# keyboard.net
KiCad netlist of a schematic drawn in Altium Designer
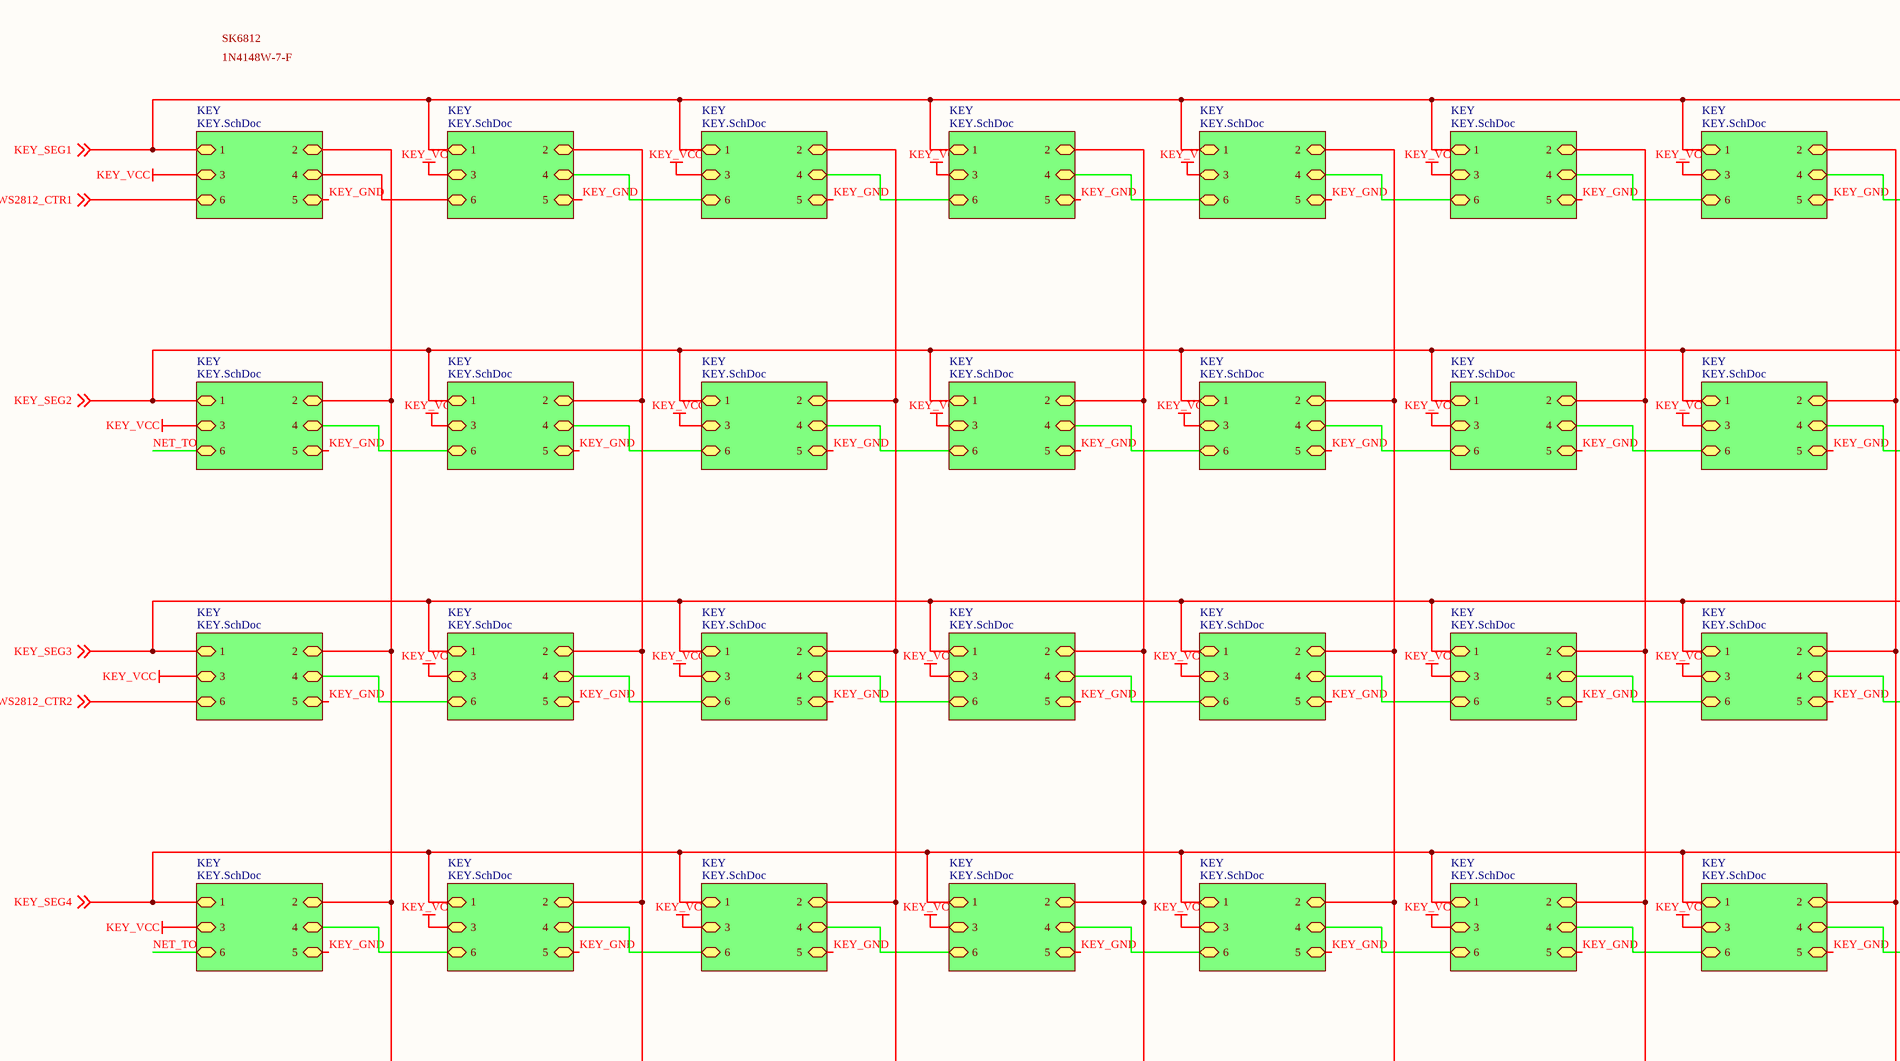
[diagram p0: keyboard.SchDoc, top left]
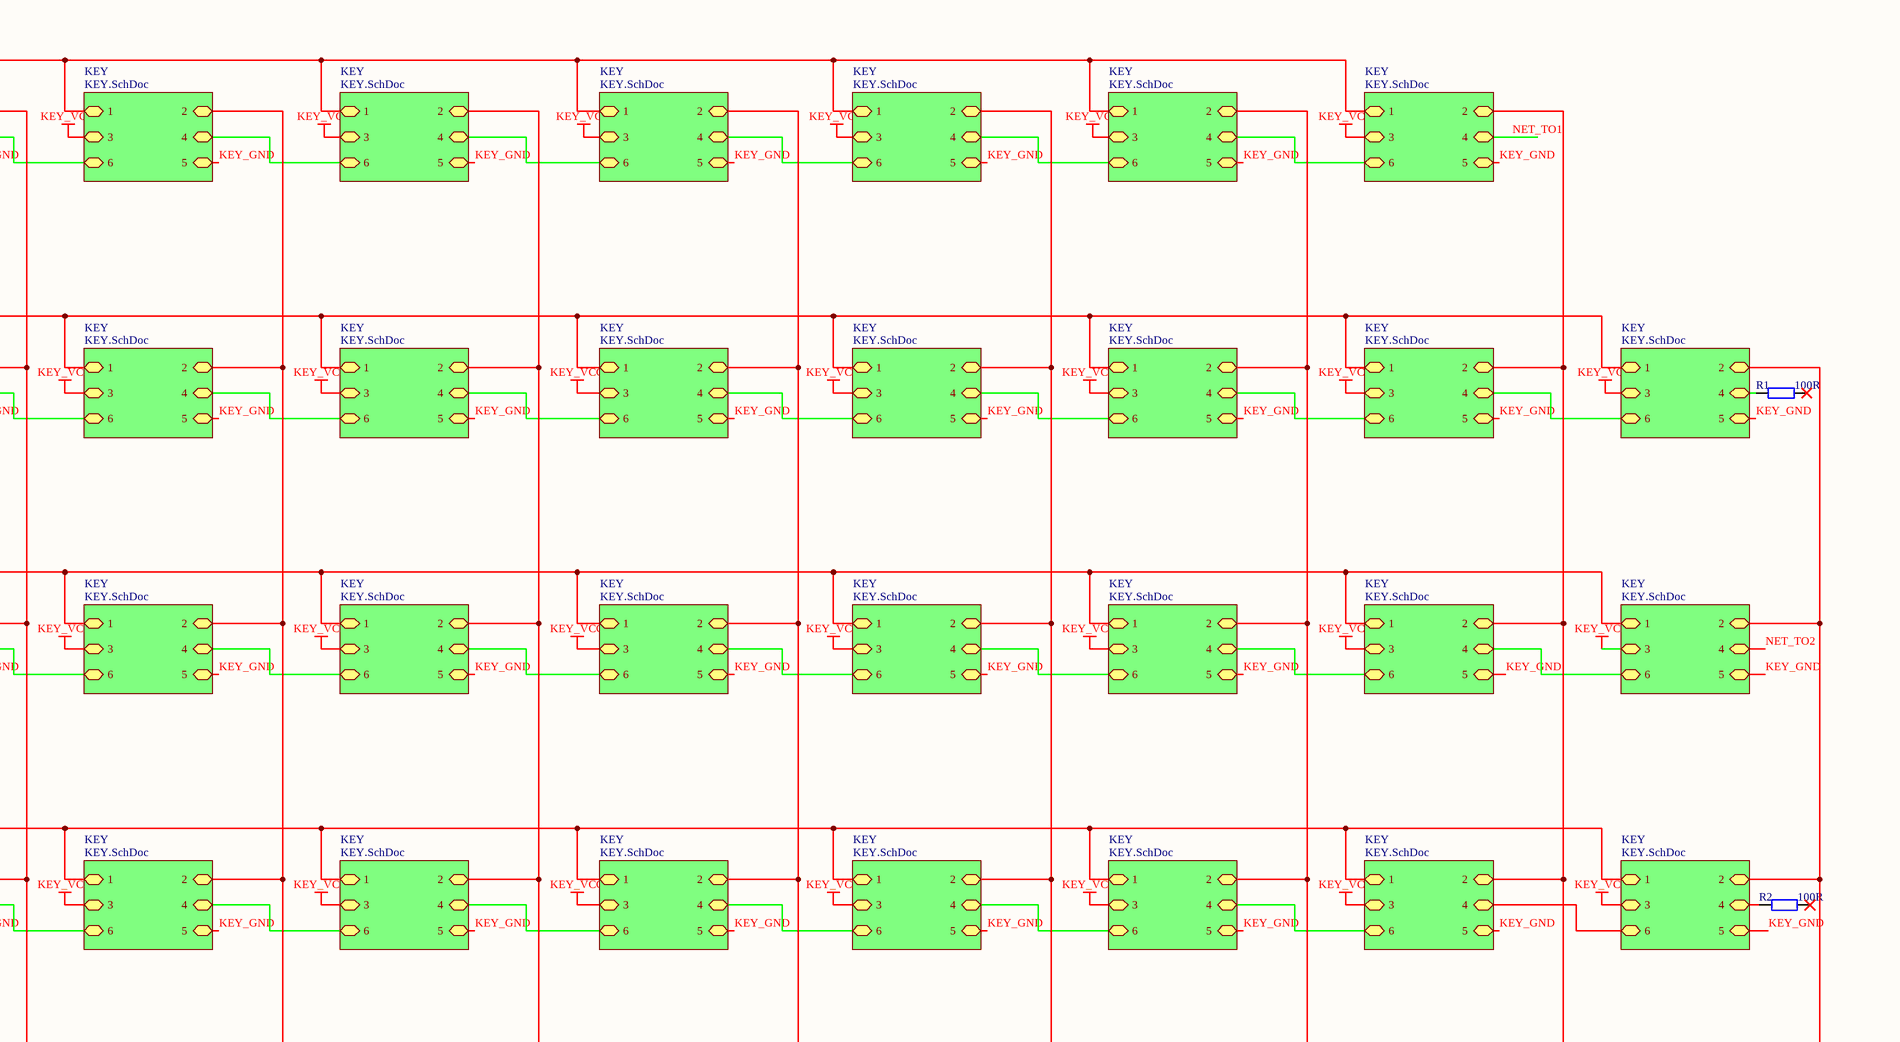
[diagram p1: keyboard.SchDoc, top right]
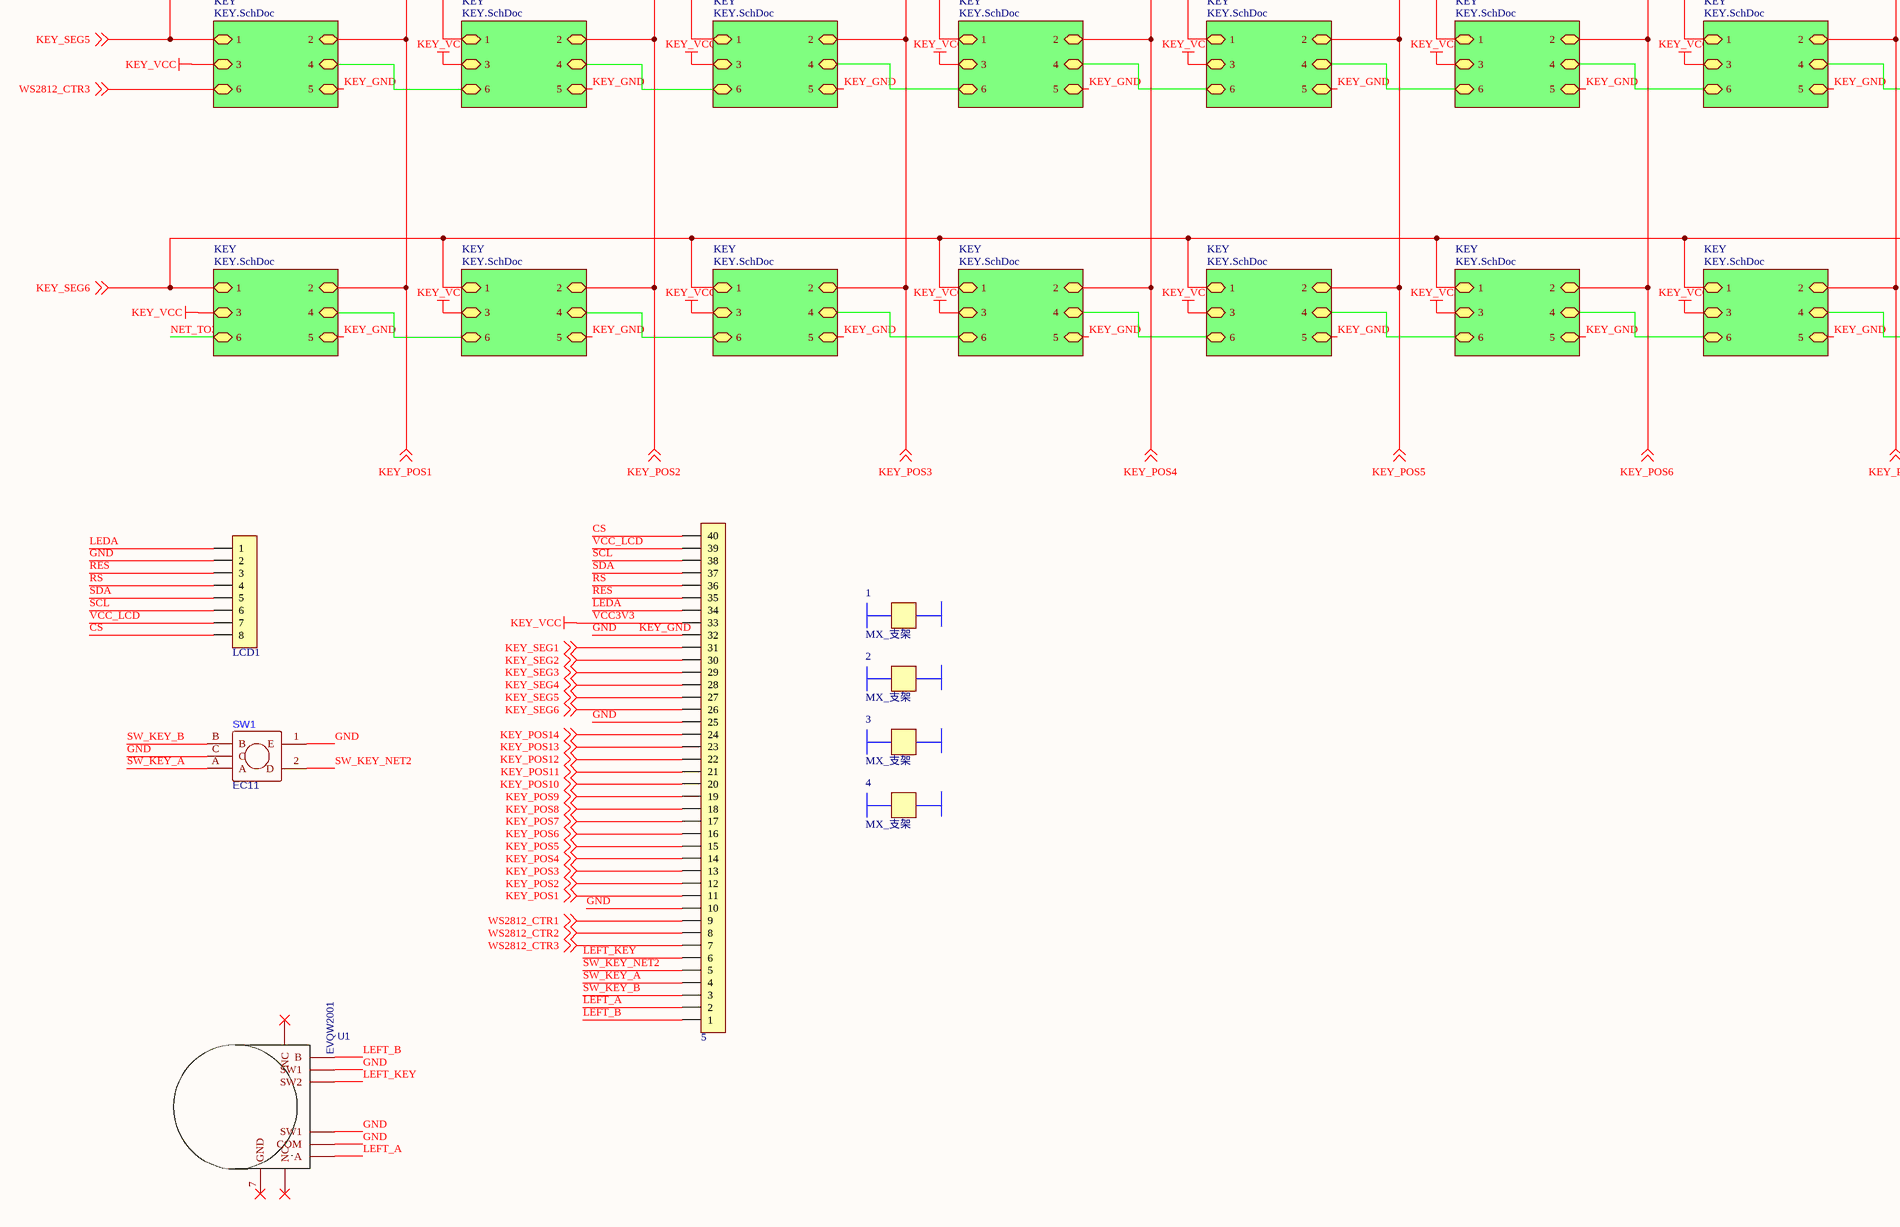
[diagram p2: keyboard.SchDoc, bottom left]
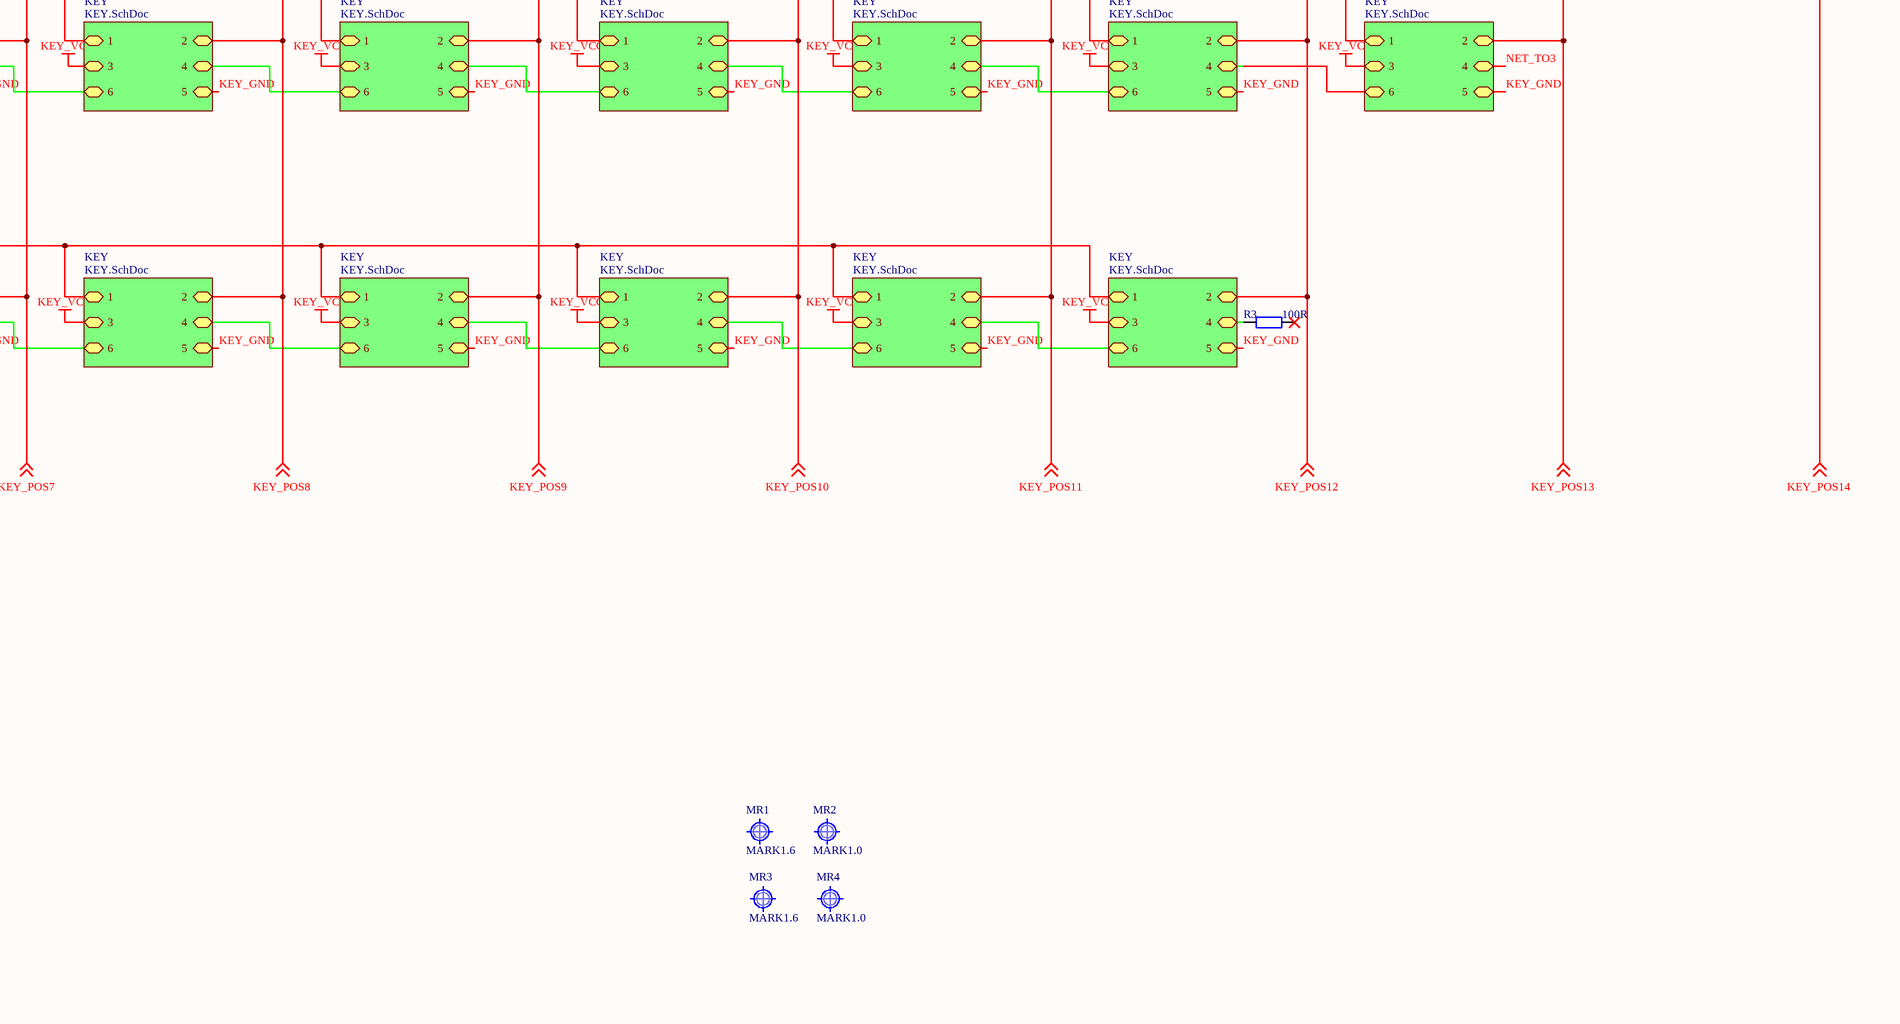
[diagram p3: keyboard.SchDoc, bottom right]

(export (version "E")
  (design (tool "Eeschema 10.0.6"))
  (components
    (comp (ref "1") (value "MX_支架") (footprint "1x2") (libsource (lib "机械键盘") (part "MX_支架")))
    (comp (ref "2") (value "MX_支架") (footprint "1x2") (libsource (lib "机械键盘") (part "MX_支架")))
    (comp (ref "3") (value "MX_支架") (footprint "1x2") (libsource (lib "机械键盘") (part "MX_支架")))
    (comp (ref "4") (value "MX_支架") (footprint "1x2") (libsource (lib "机械键盘") (part "MX_支架")))
    (comp (ref "5")
      (value "FPC1.0-40P")
      (footprint "FPC0.5 2H-WS-40P")
      (description "FPC连接器")
      (fields (field (name "版权归属") "黎明电子style"))
      (libsource (lib "FPC连接器") (part "FPC-40P"))
    )
    (comp (ref "LCD1")
      (value "FPC1.0-8P")
      (footprint "FPC0.5 2H-WS-8P")
      (description "FPC连接器")
      (fields (field (name "版权归属") "黎明电子style"))
      (libsource (lib "FPC连接器") (part "FPC-8P"))
    )
    (comp (ref "MR1")
      (value "MARK1.6")
      (footprint "Mark 1.6")
      (description "光学定位点")
      (libsource (lib "4.1 - 未分类器件") (part "MARK"))
    )
    (comp (ref "MR2")
      (value "MARK1.0")
      (footprint "Mark 1")
      (description "光学定位点")
      (libsource (lib "4.1 - 未分类器件") (part "MARK"))
    )
    (comp (ref "MR3")
      (value "MARK1.6")
      (footprint "Mark 1.6")
      (description "光学定位点")
      (libsource (lib "4.1 - 未分类器件") (part "MARK"))
    )
    (comp (ref "MR4")
      (value "MARK1.0")
      (footprint "Mark 1")
      (description "光学定位点")
      (libsource (lib "4.1 - 未分类器件") (part "MARK"))
    )
    (comp (ref "R1")
      (value "100R")
      (footprint "R 0805_M")
      (description "贴片电阻")
      (libsource (lib "0.1 - 电阻-电容-电感") (part "R"))
    )
    (comp (ref "R2")
      (value "100R")
      (footprint "R 0805_M")
      (description "贴片电阻")
      (libsource (lib "0.1 - 电阻-电容-电感") (part "R"))
    )
    (comp (ref "R3")
      (value "100R")
      (footprint "R 0805_M")
      (description "贴片电阻")
      (libsource (lib "0.1 - 电阻-电容-电感") (part "R"))
    )
    (comp (ref "SW1")
      (value "EC11")
      (footprint "BOURNS_PEC11R-4XXXF-SXXXX")
      (libsource (lib "机械键盘") (part "EC11"))
    )
    (comp (ref "U1")
      (value "EVQW2001")
      (footprint "EVQWK2001 - duplicate")
      (fields (field (name "CONTRIBUTOR") "jam_dan"))
      (libsource (lib "机械键盘") (part "EVQW2001"))
    )
  )
  (nets
    (net (code "1") (name "/4") (class "Default")
      (node (ref "R1") (pin "1") (pinfunction "1_1") (pintype "passive"))
    )
    (net (code "2") (name "/4_1") (class "Default")
      (node (ref "R3") (pin "1") (pinfunction "1_1") (pintype "passive"))
    )
    (net (code "3") (name "/4_2") (class "Default")
      (node (ref "R2") (pin "1") (pinfunction "1_1") (pintype "passive"))
    )
    (net (code "78") (name "/CS") (class "Default")
      (node (ref "5") (pin "40") (pinfunction "40_40") (pintype "passive"))
      (node (ref "LCD1") (pin "8") (pinfunction "8_8") (pintype "passive"))
    )
    (net (code "79") (name "/GND") (class "Default")
      (node (ref "5") (pin "10") (pinfunction "10_10") (pintype "passive"))
      (node (ref "5") (pin "25") (pinfunction "25_25") (pintype "passive"))
      (node (ref "5") (pin "32") (pinfunction "32_32") (pintype "passive"))
      (node (ref "LCD1") (pin "2") (pinfunction "2_2") (pintype "passive"))
      (node (ref "SW1") (pin "1") (pinfunction "E_1") (pintype "passive"))
      (node (ref "SW1") (pin "C") (pinfunction "C_C") (pintype "passive"))
      (node (ref "U1") (pin "2") (pinfunction "SW1_2") (pintype "passive"))
      (node (ref "U1") (pin "4") (pinfunction "SW1_4") (pintype "passive"))
      (node (ref "U1") (pin "5") (pinfunction "COM_5") (pintype "passive"))
    )
    (net (code "80") (name "/LEDA") (class "Default")
      (node (ref "5") (pin "34") (pinfunction "34_34") (pintype "passive"))
      (node (ref "LCD1") (pin "1") (pinfunction "1_1") (pintype "passive"))
    )
    (net (code "81") (name "/LEFT_A") (class "Default")
      (node (ref "5") (pin "2") (pinfunction "2_2") (pintype "passive"))
      (node (ref "U1") (pin "6") (pinfunction "A_6") (pintype "passive"))
    )
    (net (code "82") (name "/LEFT_B") (class "Default")
      (node (ref "5") (pin "1") (pinfunction "1_1") (pintype "passive"))
      (node (ref "U1") (pin "1") (pinfunction "B_1") (pintype "passive"))
    )
    (net (code "83") (name "/LEFT_KEY") (class "Default")
      (node (ref "5") (pin "6") (pinfunction "6_6") (pintype "passive"))
      (node (ref "U1") (pin "3") (pinfunction "SW2_3") (pintype "passive"))
    )
    (net (code "87") (name "/RES") (class "Default")
      (node (ref "5") (pin "35") (pinfunction "35_35") (pintype "passive"))
      (node (ref "LCD1") (pin "3") (pinfunction "3_3") (pintype "passive"))
    )
    (net (code "88") (name "/RS") (class "Default")
      (node (ref "5") (pin "36") (pinfunction "36_36") (pintype "passive"))
      (node (ref "LCD1") (pin "4") (pinfunction "4_4") (pintype "passive"))
    )
    (net (code "89") (name "/SCL") (class "Default")
      (node (ref "5") (pin "38") (pinfunction "38_38") (pintype "passive"))
      (node (ref "LCD1") (pin "6") (pinfunction "6_6") (pintype "passive"))
    )
    (net (code "90") (name "/SDA") (class "Default")
      (node (ref "5") (pin "37") (pinfunction "37_37") (pintype "passive"))
      (node (ref "LCD1") (pin "5") (pinfunction "5_5") (pintype "passive"))
    )
    (net (code "91") (name "/SW_KEY_A") (class "Default")
      (node (ref "5") (pin "4") (pinfunction "4_4") (pintype "passive"))
      (node (ref "SW1") (pin "A") (pinfunction "A_A") (pintype "passive"))
    )
    (net (code "92") (name "/SW_KEY_B") (class "Default")
      (node (ref "5") (pin "3") (pinfunction "3_3") (pintype "passive"))
      (node (ref "SW1") (pin "B") (pinfunction "B_B") (pintype "passive"))
    )
    (net (code "93") (name "/SW_KEY_NET2") (class "Default")
      (node (ref "5") (pin "5") (pinfunction "5_5") (pintype "passive"))
      (node (ref "SW1") (pin "2") (pinfunction "D_2") (pintype "passive"))
    )
    (net (code "94") (name "/VCC_LCD") (class "Default")
      (node (ref "5") (pin "39") (pinfunction "39_39") (pintype "passive"))
      (node (ref "LCD1") (pin "7") (pinfunction "7_7") (pintype "passive"))
    )
    (net (code "95") (name "KEY_POS1") (class "Default")
      (node (ref "5") (pin "11") (pinfunction "11_11") (pintype "passive"))
    )
    (net (code "96") (name "KEY_POS2") (class "Default")
      (node (ref "5") (pin "12") (pinfunction "12_12") (pintype "passive"))
    )
    (net (code "97") (name "KEY_POS3") (class "Default")
      (node (ref "5") (pin "13") (pinfunction "13_13") (pintype "passive"))
    )
    (net (code "98") (name "KEY_POS4") (class "Default")
      (node (ref "5") (pin "14") (pinfunction "14_14") (pintype "passive"))
    )
    (net (code "99") (name "KEY_POS5") (class "Default")
      (node (ref "5") (pin "15") (pinfunction "15_15") (pintype "passive"))
    )
    (net (code "100") (name "KEY_POS6") (class "Default")
      (node (ref "5") (pin "16") (pinfunction "16_16") (pintype "passive"))
    )
    (net (code "101") (name "KEY_POS7") (class "Default")
      (node (ref "5") (pin "17") (pinfunction "17_17") (pintype "passive"))
    )
    (net (code "102") (name "KEY_POS8") (class "Default")
      (node (ref "5") (pin "18") (pinfunction "18_18") (pintype "passive"))
    )
    (net (code "103") (name "KEY_POS9") (class "Default")
      (node (ref "5") (pin "19") (pinfunction "19_19") (pintype "passive"))
    )
    (net (code "104") (name "KEY_POS10") (class "Default")
      (node (ref "5") (pin "20") (pinfunction "20_20") (pintype "passive"))
    )
    (net (code "105") (name "KEY_POS11") (class "Default")
      (node (ref "5") (pin "21") (pinfunction "21_21") (pintype "passive"))
    )
    (net (code "106") (name "KEY_POS12") (class "Default")
      (node (ref "5") (pin "22") (pinfunction "22_22") (pintype "passive"))
    )
    (net (code "107") (name "KEY_POS13") (class "Default")
      (node (ref "5") (pin "23") (pinfunction "23_23") (pintype "passive"))
    )
    (net (code "108") (name "KEY_POS14") (class "Default")
      (node (ref "5") (pin "24") (pinfunction "24_24") (pintype "passive"))
    )
    (net (code "109") (name "KEY_SEG1") (class "Default")
      (node (ref "5") (pin "31") (pinfunction "31_31") (pintype "passive"))
    )
    (net (code "110") (name "KEY_SEG2") (class "Default")
      (node (ref "5") (pin "30") (pinfunction "30_30") (pintype "passive"))
    )
    (net (code "111") (name "KEY_SEG3") (class "Default")
      (node (ref "5") (pin "29") (pinfunction "29_29") (pintype "passive"))
    )
    (net (code "112") (name "KEY_SEG4") (class "Default")
      (node (ref "5") (pin "28") (pinfunction "28_28") (pintype "passive"))
    )
    (net (code "113") (name "KEY_SEG5") (class "Default")
      (node (ref "5") (pin "27") (pinfunction "27_27") (pintype "passive"))
    )
    (net (code "114") (name "KEY_SEG6") (class "Default")
      (node (ref "5") (pin "26") (pinfunction "26_26") (pintype "passive"))
    )
    (net (code "115") (name "KEY_VCC") (class "Default")
      (node (ref "5") (pin "33") (pinfunction "33_33") (pintype "passive"))
    )
    (net (code "116") (name "WS2812_CTR1") (class "Default")
      (node (ref "5") (pin "9") (pinfunction "9_9") (pintype "passive"))
    )
    (net (code "117") (name "WS2812_CTR2") (class "Default")
      (node (ref "5") (pin "8") (pinfunction "8_8") (pintype "passive"))
    )
    (net (code "118") (name "WS2812_CTR3") (class "Default")
      (node (ref "5") (pin "7") (pinfunction "7_7") (pintype "passive"))
    )
    (net (code "119") (name "unconnected-(R1-Pad2)") (class "Default")
      (node (ref "R1") (pin "2") (pinfunction "2_2") (pintype "passive+no_connect"))
    )
    (net (code "120") (name "unconnected-(R2-Pad2)") (class "Default")
      (node (ref "R2") (pin "2") (pinfunction "2_2") (pintype "passive+no_connect"))
    )
    (net (code "121") (name "unconnected-(R3-Pad2)") (class "Default")
      (node (ref "R3") (pin "2") (pinfunction "2_2") (pintype "passive+no_connect"))
    )
    (net (code "122") (name "unconnected-(U1-GND-Pad7)") (class "Default")
      (node (ref "U1") (pin "7") (pinfunction "GND_7") (pintype "passive+no_connect"))
    )
    (net (code "123") (name "unconnected-(U1-NC-Pad8)") (class "Default")
      (node (ref "U1") (pin "8") (pinfunction "NC_8") (pintype "passive+no_connect"))
    )
    (net (code "124") (name "unconnected-(U1-NC-Pad8)_1") (class "Default")
      (node (ref "U1") (pin "8") (pinfunction "NC_8") (pintype "passive+no_connect"))
    )
  )
)
